# combined_controller.net
KiCad netlist of a schematic drawn in EAGLE
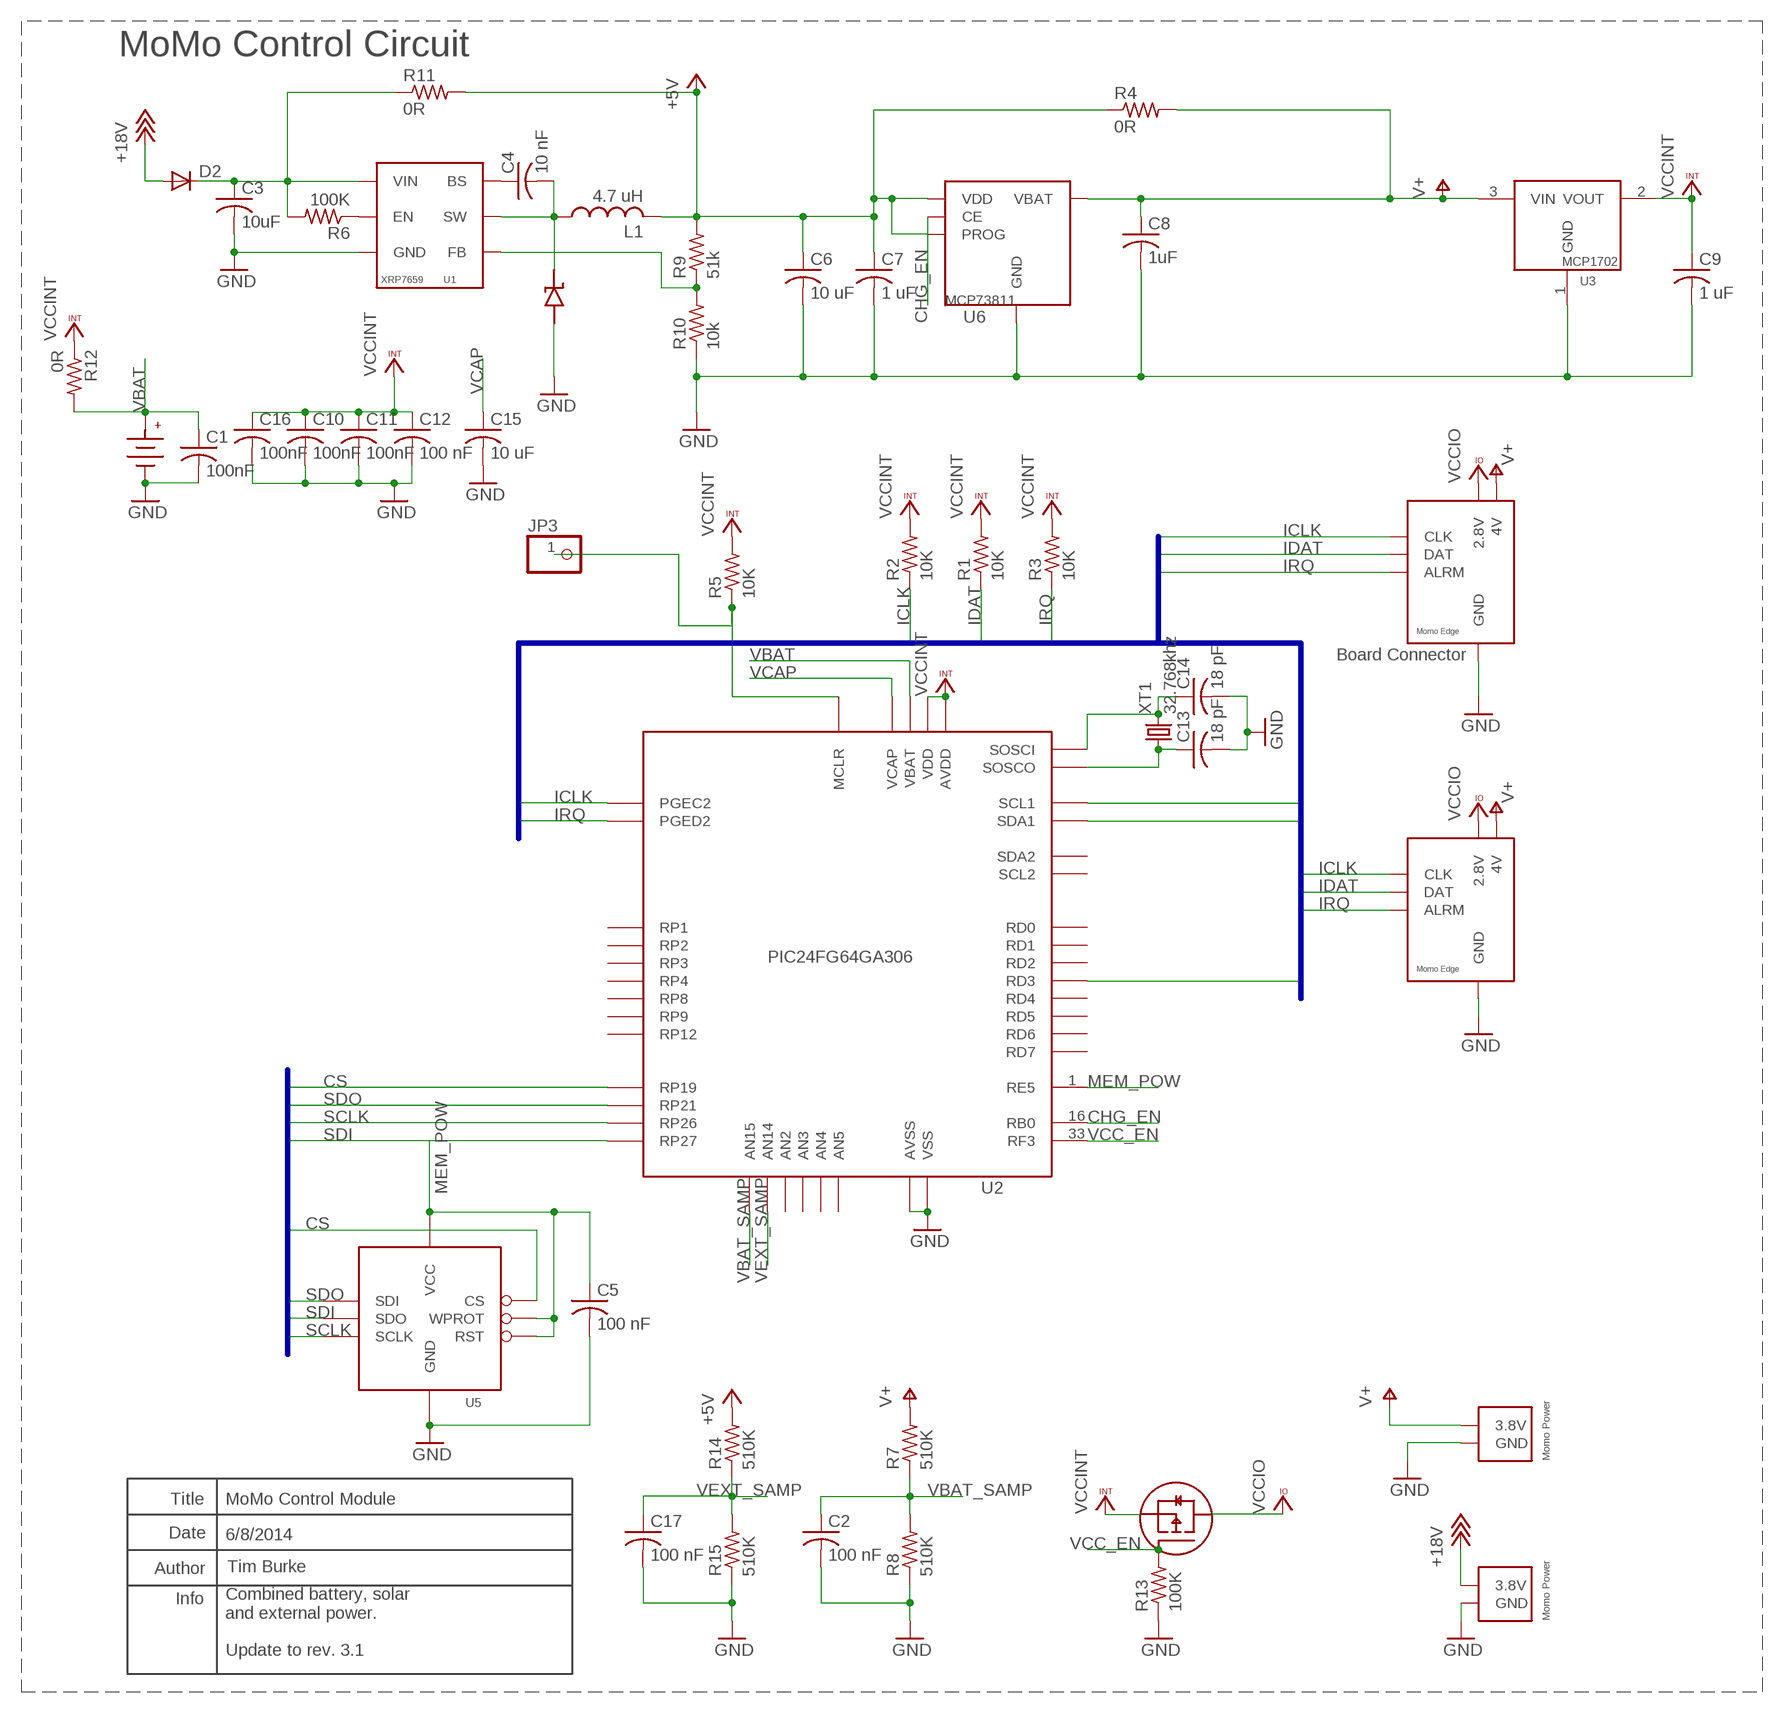
[diagram p0: schematic, sheet 1]

(export (version "E")
  (design (tool "Eeschema 10.0.6"))
  (components
    (comp (ref "BATT1")
      (value "CR1025-HOLDER")
      (footprint "eagle-import:CR1025-HOLDER")
      (libsource (lib "eagle-import") (part "CR1025-HOLDER"))
    )
    (comp (ref "C1")
      (value "100nF")
      (footprint "eagle-import:C0402")
      (libsource (lib "eagle-import") (part "C-USC0402"))
    )
    (comp (ref "C2")
      (value "100 nF")
      (footprint "eagle-import:C0402")
      (libsource (lib "eagle-import") (part "C-USC0402"))
    )
    (comp (ref "C3")
      (value "10uF")
      (footprint "eagle-import:C0805")
      (libsource (lib "eagle-import") (part "C-USC0805"))
    )
    (comp (ref "C4")
      (value "10 nF")
      (footprint "eagle-import:C0402")
      (libsource (lib "eagle-import") (part "C-USC0402"))
    )
    (comp (ref "C5")
      (value "100 nF")
      (footprint "eagle-import:C0402")
      (libsource (lib "eagle-import") (part "C-USC0402"))
    )
    (comp (ref "C6")
      (value "10 uF")
      (footprint "eagle-import:C0805")
      (libsource (lib "eagle-import") (part "C-USC0805"))
    )
    (comp (ref "C7")
      (value "1 uF")
      (footprint "eagle-import:C0402")
      (libsource (lib "eagle-import") (part "C-USC0402"))
    )
    (comp (ref "C8")
      (value "1uF")
      (footprint "eagle-import:C0402")
      (libsource (lib "eagle-import") (part "C-USC0402"))
    )
    (comp (ref "C9")
      (value "1 uF")
      (footprint "eagle-import:C0402")
      (libsource (lib "eagle-import") (part "C-USC0402"))
    )
    (comp (ref "C10")
      (value "100nF")
      (footprint "eagle-import:C0402")
      (libsource (lib "eagle-import") (part "C-USC0402"))
    )
    (comp (ref "C11")
      (value "100nF")
      (footprint "eagle-import:C0402")
      (libsource (lib "eagle-import") (part "C-USC0402"))
    )
    (comp (ref "C12")
      (value "100 nF")
      (footprint "eagle-import:C0402")
      (libsource (lib "eagle-import") (part "C-USC0402"))
    )
    (comp (ref "C13")
      (value "18 pF")
      (footprint "eagle-import:C0402K")
      (libsource (lib "eagle-import") (part "C-USC0402K"))
    )
    (comp (ref "C14")
      (value "18 pF")
      (footprint "eagle-import:C0402K")
      (libsource (lib "eagle-import") (part "C-USC0402K"))
    )
    (comp (ref "C15")
      (value "10 uF")
      (footprint "eagle-import:C0805")
      (libsource (lib "eagle-import") (part "C-USC0805"))
    )
    (comp (ref "C16")
      (value "100nF")
      (footprint "eagle-import:C0402")
      (libsource (lib "eagle-import") (part "C-USC0402"))
    )
    (comp (ref "C17")
      (value "100 nF")
      (footprint "eagle-import:C0402")
      (libsource (lib "eagle-import") (part "C-USC0402"))
    )
    (comp (ref "D1")
      (value "DIODE_SS2P3SS2P3")
      (footprint "eagle-import:DIODE_SS2P3")
      (libsource (lib "eagle-import") (part "DIODE_SS2P3SS2P3"))
    )
    (comp (ref "D2")
      (value "DIODE-DO214AC")
      (footprint "eagle-import:DO214AC")
      (description "Schottky Diode")
      (libsource (lib "eagle-import") (part "DIODE-DO214AC"))
    )
    (comp (ref "JP1")
      (value "MOMO-VERT-6M")
      (footprint "eagle-import:1X06")
      (libsource (lib "eagle-import") (part "MOMO-VERT-6M"))
    )
    (comp (ref "JP2")
      (value "MOMO-EDGE-6F")
      (footprint "eagle-import:MOMO-EDGE-8F")
      (libsource (lib "eagle-import") (part "MOMO-EDGE-6F"))
    )
    (comp (ref "JP3")
      (value "PINHD-1X1")
      (footprint "eagle-import:1X01")
      (libsource (lib "eagle-import") (part "PINHD-1X1"))
    )
    (comp (ref "JP4")
      (value "MOMO-PWR-HOUSED")
      (footprint "eagle-import:MOMO-PWR-HOUSED")
      (libsource (lib "eagle-import") (part "MOMO-PWR-HOUSED"))
    )
    (comp (ref "JP5")
      (value "MOMO-PWR-HOUSED")
      (footprint "eagle-import:MOMO-PWR-HOUSED")
      (libsource (lib "eagle-import") (part "MOMO-PWR-HOUSED"))
    )
    (comp (ref "L1")
      (value "4.7 uH")
      (footprint "eagle-import:NR6028-INDUCTOR")
      (libsource (lib "eagle-import") (part "NR6028-INDUCTOR"))
    )
    (comp (ref "Q2")
      (value "P-MOSFET")
      (footprint "eagle-import:SOT23")
      (description "P Channel MOSFET")
      (libsource (lib "eagle-import") (part "P-MOSFET"))
    )
    (comp (ref "R1")
      (value "10K")
      (footprint "eagle-import:R0603")
      (libsource (lib "eagle-import") (part "R-US_R0603"))
    )
    (comp (ref "R2")
      (value "10K")
      (footprint "eagle-import:R0603")
      (libsource (lib "eagle-import") (part "R-US_R0603"))
    )
    (comp (ref "R3")
      (value "10K")
      (footprint "eagle-import:R0603")
      (libsource (lib "eagle-import") (part "R-US_R0603"))
    )
    (comp (ref "R4")
      (value "0R")
      (footprint "eagle-import:R0603")
      (libsource (lib "eagle-import") (part "R-US_R0603"))
    )
    (comp (ref "R5")
      (value "10K")
      (footprint "eagle-import:R0603")
      (libsource (lib "eagle-import") (part "R-US_R0603"))
    )
    (comp (ref "R6")
      (value "100K")
      (footprint "eagle-import:R0603")
      (libsource (lib "eagle-import") (part "R-US_R0603"))
    )
    (comp (ref "R7")
      (value "510K")
      (footprint "eagle-import:R0603")
      (libsource (lib "eagle-import") (part "R-US_R0603"))
    )
    (comp (ref "R8")
      (value "510K")
      (footprint "eagle-import:R0603")
      (libsource (lib "eagle-import") (part "R-US_R0603"))
    )
    (comp (ref "R9")
      (value "51k")
      (footprint "eagle-import:R0603")
      (libsource (lib "eagle-import") (part "R-US_R0603"))
    )
    (comp (ref "R10")
      (value "10k")
      (footprint "eagle-import:R0603")
      (libsource (lib "eagle-import") (part "R-US_R0603"))
    )
    (comp (ref "R11")
      (value "0R")
      (footprint "eagle-import:R0603")
      (libsource (lib "eagle-import") (part "R-US_R0603"))
    )
    (comp (ref "R12")
      (value "0R")
      (footprint "eagle-import:R0603")
      (libsource (lib "eagle-import") (part "R-US_R0603"))
    )
    (comp (ref "R13")
      (value "100K")
      (footprint "eagle-import:R0603")
      (libsource (lib "eagle-import") (part "R-US_R0603"))
    )
    (comp (ref "R14")
      (value "510K")
      (footprint "eagle-import:R0603")
      (libsource (lib "eagle-import") (part "R-US_R0603"))
    )
    (comp (ref "R15")
      (value "510K")
      (footprint "eagle-import:R0603")
      (libsource (lib "eagle-import") (part "R-US_R0603"))
    )
    (comp (ref "U1")
      (value "XRP7659")
      (footprint "eagle-import:SOT23-6L")
      (libsource (lib "eagle-import") (part "XRP7659"))
    )
    (comp (ref "U2")
      (value "PIC24FJ64GA306")
      (footprint "eagle-import:TQFP64-10X10")
      (libsource (lib "eagle-import") (part "PIC24FJ64GA306"))
    )
    (comp (ref "U3")
      (value "MCP1702")
      (footprint "eagle-import:SOT23")
      (fields (field (name "DIGIKEY-PN") "MCP1702T-2802E/CBCT-ND"))
      (libsource (lib "eagle-import") (part "MCP1702"))
    )
    (comp (ref "U5")
      (value "FLASH8MSOP8")
      (footprint "eagle-import:SOP08")
      (fields (field (name "DIGIKEY-PN") "M25PX80-VMN6TPCT-ND"))
      (libsource (lib "eagle-import") (part "FLASH8MSOP8"))
    )
    (comp (ref "U6")
      (value "MCP73811")
      (footprint "eagle-import:SOT23-5L")
      (libsource (lib "eagle-import") (part "MCP73811"))
    )
    (comp (ref "XT1")
      (value "32.768khz")
      (footprint "eagle-import:TC26H")
      (libsource (lib "eagle-import") (part "XTAL-W-CAN-PAD"))
    )
  )
  (nets
    (net (code "1") (name "+5V") (class "Default")
      (node (ref "C6") (pin "1") (pinfunction "1_1") (pintype "passive"))
      (node (ref "C7") (pin "1") (pinfunction "1_1") (pintype "passive"))
      (node (ref "L1") (pin "2") (pinfunction "2_2") (pintype "passive"))
      (node (ref "R11") (pin "2") (pinfunction "2_2") (pintype "passive"))
      (node (ref "R14") (pin "2") (pinfunction "2_2") (pintype "passive"))
      (node (ref "R4") (pin "1") (pinfunction "1_1") (pintype "passive"))
      (node (ref "R9") (pin "2") (pinfunction "2_2") (pintype "passive"))
      (node (ref "U6") (pin "4") (pinfunction "VDD_4") (pintype "bidirectional"))
      (node (ref "U6") (pin "5") (pinfunction "PROG_5") (pintype "bidirectional"))
    )
    (net (code "2") (name "+18V") (class "Default")
      (node (ref "D2") (pin "A") (pinfunction "A_A") (pintype "passive"))
      (node (ref "JP4") (pin "1") (pinfunction "3.8V_1") (pintype "power_in"))
    )
    (net (code "3") (name "/CHG_EN") (class "Default")
      (node (ref "U2") (pin "16") (pinfunction "RB0_16") (pintype "bidirectional"))
      (node (ref "U6") (pin "1") (pinfunction "CE_1") (pintype "bidirectional"))
    )
    (net (code "4") (name "/CS") (class "Default")
      (node (ref "U2") (pin "6") (pinfunction "RP19_6") (pintype "bidirectional"))
      (node (ref "U5") (pin "1") (pinfunction "CS_1") (pintype "bidirectional"))
    )
    (net (code "5") (name "/ICLK") (class "Default")
      (node (ref "JP1") (pin "3") (pinfunction "CLK_3") (pintype "bidirectional"))
      (node (ref "JP2") (pin "CLK") (pinfunction "CLK_CLK") (pintype "bidirectional"))
      (node (ref "R2") (pin "1") (pinfunction "1_1") (pintype "passive"))
      (node (ref "U2") (pin "17") (pinfunction "PGEC2_17") (pintype "bidirectional"))
      (node (ref "U2") (pin "37") (pinfunction "SCL1_37") (pintype "bidirectional"))
    )
    (net (code "6") (name "/IDAT") (class "Default")
      (node (ref "JP1") (pin "4") (pinfunction "DAT_4") (pintype "bidirectional"))
      (node (ref "JP2") (pin "DAT") (pinfunction "DAT_DAT") (pintype "bidirectional"))
      (node (ref "R1") (pin "1") (pinfunction "1_1") (pintype "passive"))
      (node (ref "U2") (pin "36") (pinfunction "SDA1_36") (pintype "bidirectional"))
    )
    (net (code "7") (name "/IRQ") (class "Default")
      (node (ref "JP1") (pin "5") (pinfunction "ALRM_5") (pintype "bidirectional"))
      (node (ref "JP2") (pin "ARLM") (pinfunction "ALRM_ARLM") (pintype "bidirectional"))
      (node (ref "R3") (pin "1") (pinfunction "1_1") (pintype "passive"))
      (node (ref "U2") (pin "18") (pinfunction "PGED2_18") (pintype "bidirectional"))
      (node (ref "U2") (pin "51") (pinfunction "RD3_51") (pintype "bidirectional"))
    )
    (net (code "8") (name "/MEM_POW") (class "Default")
      (node (ref "C5") (pin "1") (pinfunction "1_1") (pintype "passive"))
      (node (ref "U2") (pin "1") (pinfunction "RE5_1") (pintype "bidirectional"))
      (node (ref "U5") (pin "3") (pinfunction "WPROT_3") (pintype "bidirectional"))
      (node (ref "U5") (pin "7") (pinfunction "RST_7") (pintype "bidirectional"))
      (node (ref "U5") (pin "8") (pinfunction "VCC_8") (pintype "power_in"))
    )
    (net (code "9") (name "/SCLK") (class "Default")
      (node (ref "U2") (pin "5") (pinfunction "RP26_5") (pintype "bidirectional"))
      (node (ref "U5") (pin "6") (pinfunction "SCLK_6") (pintype "bidirectional"))
    )
    (net (code "10") (name "/SDI") (class "Default")
      (node (ref "U2") (pin "8") (pinfunction "RP27_8") (pintype "bidirectional"))
      (node (ref "U5") (pin "2") (pinfunction "SDO_2") (pintype "bidirectional"))
    )
    (net (code "11") (name "/SDO") (class "Default")
      (node (ref "U2") (pin "4") (pinfunction "RP21_4") (pintype "bidirectional"))
      (node (ref "U5") (pin "5") (pinfunction "SDI_5") (pintype "bidirectional"))
    )
    (net (code "12") (name "/VBAT") (class "Default")
      (node (ref "BATT1") (pin "+1") (pinfunction "+_+1") (pintype "power_in"))
      (node (ref "BATT1") (pin "+2") (pinfunction "+_+2") (pintype "power_in"))
      (node (ref "C1") (pin "1") (pinfunction "1_1") (pintype "passive"))
      (node (ref "R12") (pin "2") (pinfunction "2_2") (pintype "passive"))
      (node (ref "U2") (pin "57") (pinfunction "VBAT_57") (pintype "bidirectional"))
    )
    (net (code "13") (name "/VBAT_SAMP") (class "Default")
      (node (ref "C2") (pin "1") (pinfunction "1_1") (pintype "passive"))
      (node (ref "R7") (pin "1") (pinfunction "1_1") (pintype "passive"))
      (node (ref "R8") (pin "2") (pinfunction "2_2") (pintype "passive"))
      (node (ref "U2") (pin "30") (pinfunction "AN15_30") (pintype "bidirectional"))
    )
    (net (code "14") (name "/VCAP") (class "Default")
      (node (ref "C15") (pin "1") (pinfunction "1_1") (pintype "passive"))
      (node (ref "U2") (pin "56") (pinfunction "VCAP_56") (pintype "bidirectional"))
    )
    (net (code "15") (name "/VCC_EN") (class "Default")
      (node (ref "Q2") (pin "1") (pinfunction "GATE_1") (pintype "bidirectional"))
      (node (ref "R13") (pin "2") (pinfunction "2_2") (pintype "passive"))
      (node (ref "U2") (pin "33") (pinfunction "RF3_33") (pintype "bidirectional"))
    )
    (net (code "16") (name "/VEXT_SAMP") (class "Default")
      (node (ref "C17") (pin "1") (pinfunction "1_1") (pintype "passive"))
      (node (ref "R14") (pin "1") (pinfunction "1_1") (pintype "passive"))
      (node (ref "R15") (pin "2") (pinfunction "2_2") (pintype "passive"))
      (node (ref "U2") (pin "29") (pinfunction "AN14_29") (pintype "bidirectional"))
    )
    (net (code "17") (name "GND") (class "Default")
      (node (ref "BATT1") (pin "-") (pinfunction "-_-") (pintype "power_in"))
      (node (ref "C1") (pin "2") (pinfunction "2_2") (pintype "passive"))
      (node (ref "C10") (pin "2") (pinfunction "2_2") (pintype "passive"))
      (node (ref "C11") (pin "2") (pinfunction "2_2") (pintype "passive"))
      (node (ref "C12") (pin "2") (pinfunction "2_2") (pintype "passive"))
      (node (ref "C13") (pin "2") (pinfunction "2_2") (pintype "passive"))
      (node (ref "C14") (pin "2") (pinfunction "2_2") (pintype "passive"))
      (node (ref "C15") (pin "2") (pinfunction "2_2") (pintype "passive"))
      (node (ref "C16") (pin "2") (pinfunction "2_2") (pintype "passive"))
      (node (ref "C17") (pin "2") (pinfunction "2_2") (pintype "passive"))
      (node (ref "C2") (pin "2") (pinfunction "2_2") (pintype "passive"))
      (node (ref "C3") (pin "2") (pinfunction "2_2") (pintype "passive"))
      (node (ref "C5") (pin "2") (pinfunction "2_2") (pintype "passive"))
      (node (ref "C6") (pin "2") (pinfunction "2_2") (pintype "passive"))
      (node (ref "C7") (pin "2") (pinfunction "2_2") (pintype "passive"))
      (node (ref "C8") (pin "2") (pinfunction "2_2") (pintype "passive"))
      (node (ref "C9") (pin "2") (pinfunction "2_2") (pintype "passive"))
      (node (ref "D1") (pin "AN") (pinfunction "AN_AN") (pintype "bidirectional"))
      (node (ref "JP1") (pin "7") (pinfunction "GND_7") (pintype "power_in"))
      (node (ref "JP2") (pin "GND") (pinfunction "GND_GND") (pintype "power_in"))
      (node (ref "JP4") (pin "2") (pinfunction "GND_2") (pintype "power_in"))
      (node (ref "JP5") (pin "2") (pinfunction "GND_2") (pintype "power_in"))
      (node (ref "R10") (pin "1") (pinfunction "1_1") (pintype "passive"))
      (node (ref "R13") (pin "1") (pinfunction "1_1") (pintype "passive"))
      (node (ref "R15") (pin "1") (pinfunction "1_1") (pintype "passive"))
      (node (ref "R8") (pin "1") (pinfunction "1_1") (pintype "passive"))
      (node (ref "U1") (pin "2") (pinfunction "GND_2") (pintype "bidirectional"))
      (node (ref "U2") (pin "20") (pinfunction "AVSS_20") (pintype "bidirectional"))
      (node (ref "U2") (pin "25") (pinfunction "VSS_25") (pintype "bidirectional"))
      (node (ref "U2") (pin "41") (pinfunction "VSS_41") (pintype "bidirectional"))
      (node (ref "U2") (pin "9") (pinfunction "VSS_9") (pintype "bidirectional"))
      (node (ref "U3") (pin "1") (pinfunction "GND_1") (pintype "bidirectional"))
      (node (ref "U5") (pin "4") (pinfunction "GND_4") (pintype "power_in"))
      (node (ref "U6") (pin "2") (pinfunction "GND_2") (pintype "bidirectional"))
    )
    (net (code "18") (name "Net-(U1-BS)") (class "Default")
      (node (ref "C4") (pin "1") (pinfunction "1_1") (pintype "passive"))
      (node (ref "U1") (pin "1") (pinfunction "BS_1") (pintype "bidirectional"))
    )
    (net (code "19") (name "Net-(U1-EN)") (class "Default")
      (node (ref "R6") (pin "1") (pinfunction "1_1") (pintype "passive"))
      (node (ref "U1") (pin "4") (pinfunction "EN_4") (pintype "bidirectional"))
    )
    (net (code "20") (name "Net-(U1-FB)") (class "Default")
      (node (ref "R10") (pin "2") (pinfunction "2_2") (pintype "passive"))
      (node (ref "R9") (pin "1") (pinfunction "1_1") (pintype "passive"))
      (node (ref "U1") (pin "3") (pinfunction "FB_3") (pintype "bidirectional"))
    )
    (net (code "21") (name "Net-(U1-SW)") (class "Default")
      (node (ref "C4") (pin "2") (pinfunction "2_2") (pintype "passive"))
      (node (ref "D1") (pin "CATH") (pinfunction "CATH_CATH") (pintype "bidirectional"))
      (node (ref "L1") (pin "1") (pinfunction "1_1") (pintype "passive"))
      (node (ref "U1") (pin "6") (pinfunction "SW_6") (pintype "bidirectional"))
    )
    (net (code "22") (name "Net-(U1-VIN)") (class "Default")
      (node (ref "C3") (pin "1") (pinfunction "1_1") (pintype "passive"))
      (node (ref "D2") (pin "C") (pinfunction "C_C") (pintype "passive"))
      (node (ref "R11") (pin "1") (pinfunction "1_1") (pintype "passive"))
      (node (ref "R6") (pin "2") (pinfunction "2_2") (pintype "passive"))
      (node (ref "U1") (pin "5") (pinfunction "VIN_5") (pintype "bidirectional"))
    )
    (net (code "23") (name "Net-(U2-MCLR)") (class "Default")
      (node (ref "JP3") (pin "1") (pinfunction "1_1") (pintype "passive"))
      (node (ref "R5") (pin "1") (pinfunction "1_1") (pintype "passive"))
      (node (ref "U2") (pin "7") (pinfunction "MCLR_7") (pintype "bidirectional"))
    )
    (net (code "24") (name "Net-(U2-SOSCI)") (class "Default")
      (node (ref "C14") (pin "1") (pinfunction "1_1") (pintype "passive"))
      (node (ref "U2") (pin "47") (pinfunction "SOSCI_47") (pintype "bidirectional"))
      (node (ref "XT1") (pin "2") (pinfunction "2_2") (pintype "passive"))
    )
    (net (code "25") (name "Net-(U2-SOSCO)") (class "Default")
      (node (ref "C13") (pin "1") (pinfunction "1_1") (pintype "passive"))
      (node (ref "U2") (pin "48") (pinfunction "SOSCO_48") (pintype "bidirectional"))
      (node (ref "XT1") (pin "1") (pinfunction "1_1") (pintype "passive"))
    )
    (net (code "26") (name "V+") (class "Default")
      (node (ref "C8") (pin "1") (pinfunction "1_1") (pintype "passive"))
      (node (ref "JP1") (pin "6") (pinfunction "4V_6") (pintype "power_in"))
      (node (ref "JP2") (pin "V4") (pinfunction "4V_V4") (pintype "power_in"))
      (node (ref "JP5") (pin "1") (pinfunction "3.8V_1") (pintype "power_in"))
      (node (ref "R4") (pin "2") (pinfunction "2_2") (pintype "passive"))
      (node (ref "R7") (pin "2") (pinfunction "2_2") (pintype "passive"))
      (node (ref "U3") (pin "3") (pinfunction "VIN_3") (pintype "bidirectional"))
      (node (ref "U6") (pin "3") (pinfunction "VBAT_3") (pintype "bidirectional"))
    )
    (net (code "27") (name "VCCINT") (class "Default")
      (node (ref "C10") (pin "1") (pinfunction "1_1") (pintype "passive"))
      (node (ref "C11") (pin "1") (pinfunction "1_1") (pintype "passive"))
      (node (ref "C12") (pin "1") (pinfunction "1_1") (pintype "passive"))
      (node (ref "C16") (pin "1") (pinfunction "1_1") (pintype "passive"))
      (node (ref "C9") (pin "1") (pinfunction "1_1") (pintype "passive"))
      (node (ref "Q2") (pin "2") (pinfunction "SOURCE_2") (pintype "bidirectional"))
      (node (ref "R1") (pin "2") (pinfunction "2_2") (pintype "passive"))
      (node (ref "R12") (pin "1") (pinfunction "1_1") (pintype "passive"))
      (node (ref "R2") (pin "2") (pinfunction "2_2") (pintype "passive"))
      (node (ref "R3") (pin "2") (pinfunction "2_2") (pintype "passive"))
      (node (ref "R5") (pin "2") (pinfunction "2_2") (pintype "passive"))
      (node (ref "U2") (pin "10") (pinfunction "VDD_10") (pintype "bidirectional"))
      (node (ref "U2") (pin "19") (pinfunction "AVDD_19") (pintype "bidirectional"))
      (node (ref "U2") (pin "26") (pinfunction "VDD_26") (pintype "bidirectional"))
      (node (ref "U2") (pin "38") (pinfunction "VDD_38") (pintype "bidirectional"))
      (node (ref "U3") (pin "2") (pinfunction "VOUT_2") (pintype "bidirectional"))
    )
    (net (code "28") (name "VCCIO") (class "Default")
      (node (ref "JP1") (pin "1") (pinfunction "2.8V_1") (pintype "power_in"))
      (node (ref "JP2") (pin "V28") (pinfunction "2.8V_V28") (pintype "power_in"))
      (node (ref "Q2") (pin "3") (pinfunction "DRAIN_3") (pintype "bidirectional"))
    )
    (net (code "29") (name "unconnected-(U2-AN2-Pad14)") (class "Default")
      (node (ref "U2") (pin "14") (pinfunction "AN2_14") (pintype "bidirectional"))
    )
    (net (code "30") (name "unconnected-(U2-AN3-Pad13)") (class "Default")
      (node (ref "U2") (pin "13") (pinfunction "AN3_13") (pintype "bidirectional"))
    )
    (net (code "31") (name "unconnected-(U2-AN4-Pad12)") (class "Default")
      (node (ref "U2") (pin "12") (pinfunction "AN4_12") (pintype "bidirectional"))
    )
    (net (code "32") (name "unconnected-(U2-AN5-Pad11)") (class "Default")
      (node (ref "U2") (pin "11") (pinfunction "AN5_11") (pintype "bidirectional"))
    )
    (net (code "33") (name "unconnected-(U2-RD0-Pad46)") (class "Default")
      (node (ref "U2") (pin "46") (pinfunction "RD0_46") (pintype "bidirectional"))
    )
    (net (code "34") (name "unconnected-(U2-RD1-Pad49)") (class "Default")
      (node (ref "U2") (pin "49") (pinfunction "RD1_49") (pintype "bidirectional"))
    )
    (net (code "35") (name "unconnected-(U2-RD2-Pad50)") (class "Default")
      (node (ref "U2") (pin "50") (pinfunction "RD2_50") (pintype "bidirectional"))
    )
    (net (code "36") (name "unconnected-(U2-RD4-Pad52)") (class "Default")
      (node (ref "U2") (pin "52") (pinfunction "RD4_52") (pintype "bidirectional"))
    )
    (net (code "37") (name "unconnected-(U2-RD5-Pad53)") (class "Default")
      (node (ref "U2") (pin "53") (pinfunction "RD5_53") (pintype "bidirectional"))
    )
    (net (code "38") (name "unconnected-(U2-RD6-Pad54)") (class "Default")
      (node (ref "U2") (pin "54") (pinfunction "RD6_54") (pintype "bidirectional"))
    )
    (net (code "39") (name "unconnected-(U2-RD7-Pad55)") (class "Default")
      (node (ref "U2") (pin "55") (pinfunction "RD7_55") (pintype "bidirectional"))
    )
    (net (code "40") (name "unconnected-(U2-RP1-Pad15)") (class "Default")
      (node (ref "U2") (pin "15") (pinfunction "RP1_15") (pintype "bidirectional"))
    )
    (net (code "41") (name "unconnected-(U2-RP2-Pad42)") (class "Default")
      (node (ref "U2") (pin "42") (pinfunction "RP2_42") (pintype "bidirectional"))
    )
    (net (code "42") (name "unconnected-(U2-RP3-Pad44)") (class "Default")
      (node (ref "U2") (pin "44") (pinfunction "RP3_44") (pintype "bidirectional"))
    )
    (net (code "43") (name "unconnected-(U2-RP4-Pad43)") (class "Default")
      (node (ref "U2") (pin "43") (pinfunction "RP4_43") (pintype "bidirectional"))
    )
    (net (code "44") (name "unconnected-(U2-RP8-Pad21)") (class "Default")
      (node (ref "U2") (pin "21") (pinfunction "RP8_21") (pintype "bidirectional"))
    )
    (net (code "45") (name "unconnected-(U2-RP9-Pad22)") (class "Default")
      (node (ref "U2") (pin "22") (pinfunction "RP9_22") (pintype "bidirectional"))
    )
    (net (code "46") (name "unconnected-(U2-RP12-Pad45)") (class "Default")
      (node (ref "U2") (pin "45") (pinfunction "RP12_45") (pintype "bidirectional"))
    )
    (net (code "47") (name "unconnected-(U2-SCL2-Pad32)") (class "Default")
      (node (ref "U2") (pin "32") (pinfunction "SCL2_32") (pintype "bidirectional"))
    )
    (net (code "48") (name "unconnected-(U2-SDA2-Pad31)") (class "Default")
      (node (ref "U2") (pin "31") (pinfunction "SDA2_31") (pintype "bidirectional"))
    )
  )
)
